# FPGA_IO.net
KiCad netlist of a schematic drawn in Altium Designer
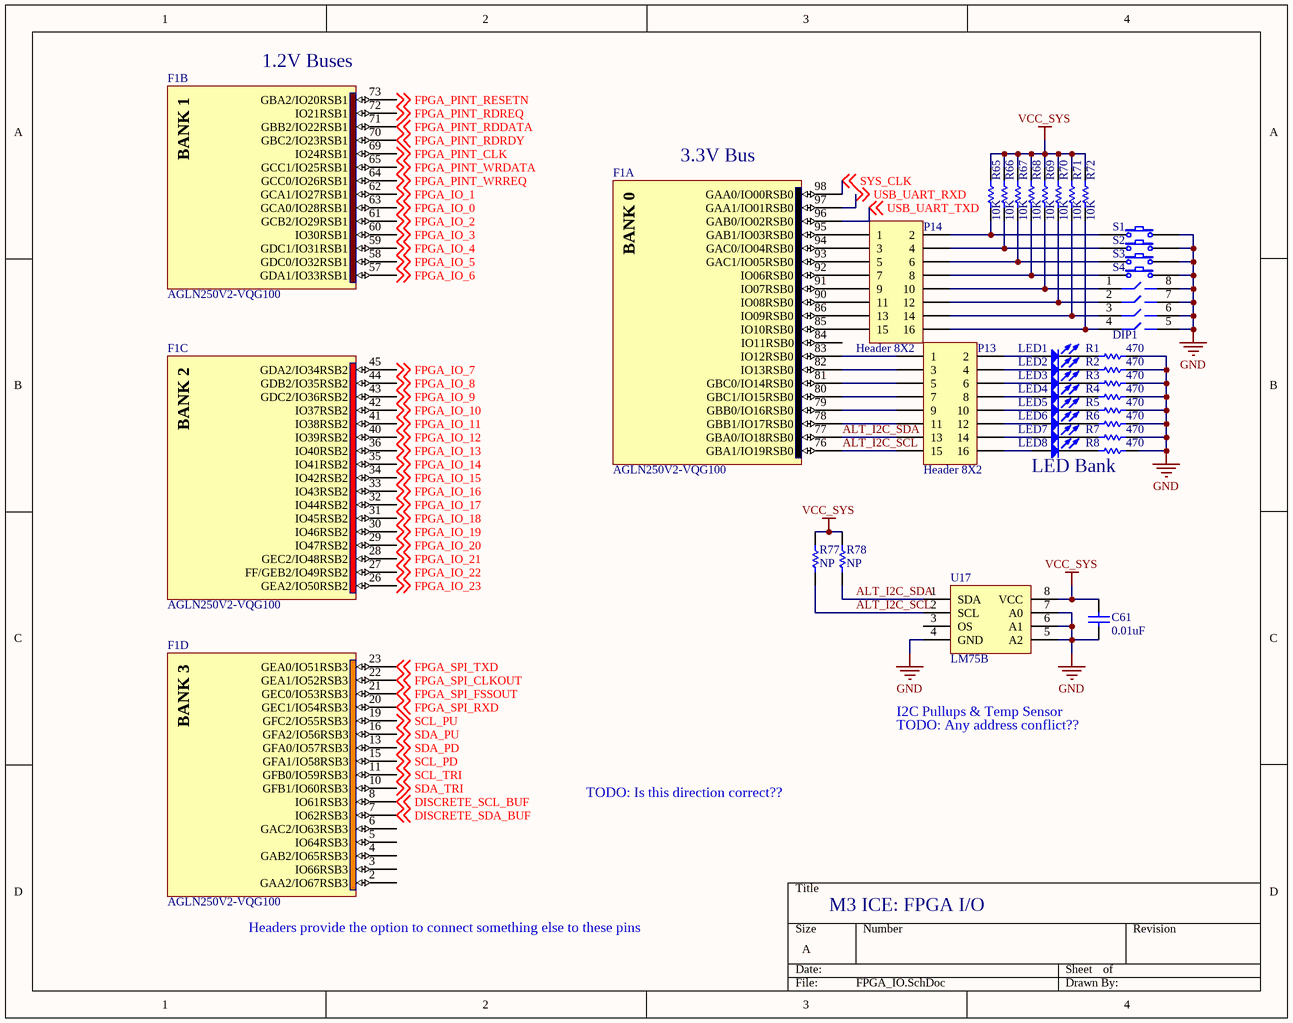
[diagram p0: FPGA_IO.SchDoc]

(export (version "E")
  (design (tool "Eeschema 10.0.6"))
  (components
    (comp (ref "C61")
      (value "0.01uF")
      (footprint "1608[0603]")
      (description "Capacitor (Semiconductor SIM Model)")
      (fields (field (name "Comment") "Cap Semi") (field (name "PUBLISHER") "Altium Limited"))
      (libsource (lib "Miscellaneous Devices") (part "Cap Semi"))
    )
    (comp (ref "DIP1")
      (value "ADE0404")
      (footprint "DIP-8")
      (description "4-DIP Switch")
      (fields (field (name "PUBLISHER") "Altium Limited"))
      (libsource (lib "M3") (part "ADE0404"))
    )
    (comp (ref "F1")
      (value "AGLN250V2-VQG100")
      (footprint "VQ100_N")
      (fields (field (name "PUBLISHER") "Altium Limited"))
      (libsource (lib "Actel IGLOO nano") (part "AGLN250V2-VQG100"))
    )
    (comp (ref "LED1") (value "LED 1206") (footprint "1206_LED") (libsource (lib "M3") (part "LED 1206")))
    (comp (ref "LED2") (value "LED 1206") (footprint "1206_LED") (libsource (lib "M3") (part "LED 1206")))
    (comp (ref "LED3") (value "LED 1206") (footprint "1206_LED") (libsource (lib "M3") (part "LED 1206")))
    (comp (ref "LED4") (value "LED 1206") (footprint "1206_LED") (libsource (lib "M3") (part "LED 1206")))
    (comp (ref "LED5") (value "LED 1206") (footprint "1206_LED") (libsource (lib "M3") (part "LED 1206")))
    (comp (ref "LED6") (value "LED 1206") (footprint "1206_LED") (libsource (lib "M3") (part "LED 1206")))
    (comp (ref "LED7") (value "LED 1206") (footprint "1206_LED") (libsource (lib "M3") (part "LED 1206")))
    (comp (ref "LED8") (value "LED 1206") (footprint "1206_LED") (libsource (lib "M3") (part "LED 1206")))
    (comp (ref "P13")
      (value "Header 8X2")
      (footprint "HDR2X8")
      (description "Header, 8-Pin, Dual row")
      (fields (field (name "PUBLISHER") "Altium Limited"))
      (libsource (lib "Miscellaneous Connectors") (part "Header 8X2"))
    )
    (comp (ref "P14")
      (value "Header 8X2")
      (footprint "HDR2X8")
      (description "Header, 8-Pin, Dual row")
      (fields (field (name "PUBLISHER") "Altium Limited"))
      (libsource (lib "Miscellaneous Connectors") (part "Header 8X2"))
    )
    (comp (ref "R1")
      (value "470")
      (footprint "0603")
      (description "Semiconductor Resistor")
      (fields (field (name "Comment") "Res Chip") (field (name "PUBLISHER") "Altium Limited"))
      (libsource (lib "M3") (part "Res Chip"))
    )
    (comp (ref "R2")
      (value "470")
      (footprint "0603")
      (description "Semiconductor Resistor")
      (fields (field (name "Comment") "Res Chip") (field (name "PUBLISHER") "Altium Limited"))
      (libsource (lib "M3") (part "Res Chip"))
    )
    (comp (ref "R3")
      (value "470")
      (footprint "0603")
      (description "Semiconductor Resistor")
      (fields (field (name "Comment") "Res Chip") (field (name "PUBLISHER") "Altium Limited"))
      (libsource (lib "M3") (part "Res Chip"))
    )
    (comp (ref "R4")
      (value "470")
      (footprint "0603")
      (description "Semiconductor Resistor")
      (fields (field (name "Comment") "Res Chip") (field (name "PUBLISHER") "Altium Limited"))
      (libsource (lib "M3") (part "Res Chip"))
    )
    (comp (ref "R5")
      (value "470")
      (footprint "0603")
      (description "Semiconductor Resistor")
      (fields (field (name "Comment") "Res Chip") (field (name "PUBLISHER") "Altium Limited"))
      (libsource (lib "M3") (part "Res Chip"))
    )
    (comp (ref "R6")
      (value "470")
      (footprint "0603")
      (description "Semiconductor Resistor")
      (fields (field (name "Comment") "Res Chip") (field (name "PUBLISHER") "Altium Limited"))
      (libsource (lib "M3") (part "Res Chip"))
    )
    (comp (ref "R7")
      (value "470")
      (footprint "0603")
      (description "Semiconductor Resistor")
      (fields (field (name "Comment") "Res Chip") (field (name "PUBLISHER") "Altium Limited"))
      (libsource (lib "M3") (part "Res Chip"))
    )
    (comp (ref "R8")
      (value "470")
      (footprint "0603")
      (description "Semiconductor Resistor")
      (fields (field (name "Comment") "Res Chip") (field (name "PUBLISHER") "Altium Limited"))
      (libsource (lib "M3") (part "Res Chip"))
    )
    (comp (ref "R65")
      (value "10K")
      (footprint "0603")
      (description "Semiconductor Resistor")
      (fields (field (name "Comment") "Res Chip") (field (name "PUBLISHER") "Altium Limited"))
      (libsource (lib "M3") (part "Res Chip"))
    )
    (comp (ref "R66")
      (value "10K")
      (footprint "0603")
      (description "Semiconductor Resistor")
      (fields (field (name "Comment") "Res Chip") (field (name "PUBLISHER") "Altium Limited"))
      (libsource (lib "M3") (part "Res Chip"))
    )
    (comp (ref "R67")
      (value "10K")
      (footprint "0603")
      (description "Semiconductor Resistor")
      (fields (field (name "Comment") "Res Chip") (field (name "PUBLISHER") "Altium Limited"))
      (libsource (lib "M3") (part "Res Chip"))
    )
    (comp (ref "R68")
      (value "10K")
      (footprint "0603")
      (description "Semiconductor Resistor")
      (fields (field (name "Comment") "Res Chip") (field (name "PUBLISHER") "Altium Limited"))
      (libsource (lib "M3") (part "Res Chip"))
    )
    (comp (ref "R69")
      (value "10K")
      (footprint "0603")
      (description "Semiconductor Resistor")
      (fields (field (name "Comment") "Res Chip") (field (name "PUBLISHER") "Altium Limited"))
      (libsource (lib "M3") (part "Res Chip"))
    )
    (comp (ref "R70")
      (value "10K")
      (footprint "0603")
      (description "Semiconductor Resistor")
      (fields (field (name "Comment") "Res Chip") (field (name "PUBLISHER") "Altium Limited"))
      (libsource (lib "M3") (part "Res Chip"))
    )
    (comp (ref "R71")
      (value "10K")
      (footprint "0603")
      (description "Semiconductor Resistor")
      (fields (field (name "Comment") "Res Chip") (field (name "PUBLISHER") "Altium Limited"))
      (libsource (lib "M3") (part "Res Chip"))
    )
    (comp (ref "R72")
      (value "10K")
      (footprint "0603")
      (description "Semiconductor Resistor")
      (fields (field (name "Comment") "Res Chip") (field (name "PUBLISHER") "Altium Limited"))
      (libsource (lib "M3") (part "Res Chip"))
    )
    (comp (ref "R77")
      (value "NP")
      (footprint "0603")
      (description "Semiconductor Resistor")
      (fields (field (name "Comment") "Res Chip") (field (name "PUBLISHER") "Altium Limited"))
      (libsource (lib "M3") (part "Res Chip"))
    )
    (comp (ref "R78")
      (value "NP")
      (footprint "0603")
      (description "Semiconductor Resistor")
      (fields (field (name "Comment") "Res Chip") (field (name "PUBLISHER") "Altium Limited"))
      (libsource (lib "M3") (part "Res Chip"))
    )
    (comp (ref "S1")
      (value "EVQ-PAE04M")
      (footprint "EVQPA")
      (description "Switch Push")
      (fields (field (name "PUBLISHER") "Altium Limited"))
      (libsource (lib "M3") (part "EVQ-PAE04M"))
    )
    (comp (ref "S2")
      (value "EVQ-PAE04M")
      (footprint "EVQPA")
      (description "Switch Push")
      (fields (field (name "PUBLISHER") "Altium Limited"))
      (libsource (lib "M3") (part "EVQ-PAE04M"))
    )
    (comp (ref "S3")
      (value "EVQ-PAE04M")
      (footprint "EVQPA")
      (description "Switch Push")
      (fields (field (name "PUBLISHER") "Altium Limited"))
      (libsource (lib "M3") (part "EVQ-PAE04M"))
    )
    (comp (ref "S4")
      (value "EVQ-PAE04M")
      (footprint "EVQPA")
      (description "Switch Push")
      (fields (field (name "PUBLISHER") "Altium Limited"))
      (libsource (lib "M3") (part "EVQ-PAE04M"))
    )
    (comp (ref "U17")
      (value "LM75B")
      (footprint "SO8")
      (description "I2C Temp Sensor")
      (libsource (lib "M3") (part "LM75B"))
    )
  )
  (nets
    (net (code "1") (name "/ALT_I2C_SCL") (class "Default")
      (node (ref "F1") (pin "76") (pinfunction "GBA1/IO19RSB0_76") (pintype "bidirectional"))
      (node (ref "P13") (pin "15") (pinfunction "15_15") (pintype "passive"))
      (node (ref "R77") (pin "2") (pinfunction "2_2") (pintype "passive"))
      (node (ref "U17") (pin "2") (pinfunction "SCL_2") (pintype "passive"))
    )
    (net (code "2") (name "/ALT_I2C_SDA") (class "Default")
      (node (ref "F1") (pin "77") (pinfunction "GBA0/IO18RSB0_77") (pintype "bidirectional"))
      (node (ref "P13") (pin "13") (pinfunction "13_13") (pintype "passive"))
      (node (ref "R78") (pin "2") (pinfunction "2_2") (pintype "passive"))
      (node (ref "U17") (pin "1") (pinfunction "SDA_1") (pintype "passive"))
    )
    (net (code "3") (name "DISCRETE_SCL_BUF") (class "Default")
      (node (ref "F1") (pin "8") (pinfunction "IO61RSB3_8") (pintype "bidirectional"))
    )
    (net (code "4") (name "DISCRETE_SDA_BUF") (class "Default")
      (node (ref "F1") (pin "7") (pinfunction "IO62RSB3_7") (pintype "bidirectional"))
    )
    (net (code "5") (name "FPGA_IO_0") (class "Default")
      (node (ref "F1") (pin "63") (pinfunction "GCA0/IO28RSB1_63") (pintype "bidirectional"))
    )
    (net (code "6") (name "FPGA_IO_1") (class "Default")
      (node (ref "F1") (pin "62") (pinfunction "GCA1/IO27RSB1_62") (pintype "bidirectional"))
    )
    (net (code "7") (name "FPGA_IO_2") (class "Default")
      (node (ref "F1") (pin "61") (pinfunction "GCB2/IO29RSB1_61") (pintype "bidirectional"))
    )
    (net (code "8") (name "FPGA_IO_3") (class "Default")
      (node (ref "F1") (pin "60") (pinfunction "IO30RSB1_60") (pintype "bidirectional"))
    )
    (net (code "9") (name "FPGA_IO_4") (class "Default")
      (node (ref "F1") (pin "59") (pinfunction "GDC1/IO31RSB1_59") (pintype "bidirectional"))
    )
    (net (code "10") (name "FPGA_IO_5") (class "Default")
      (node (ref "F1") (pin "58") (pinfunction "GDC0/IO32RSB1_58") (pintype "bidirectional"))
    )
    (net (code "11") (name "FPGA_IO_6") (class "Default")
      (node (ref "F1") (pin "57") (pinfunction "GDA1/IO33RSB1_57") (pintype "bidirectional"))
    )
    (net (code "12") (name "FPGA_IO_7") (class "Default")
      (node (ref "F1") (pin "45") (pinfunction "GDA2/IO34RSB2_45") (pintype "bidirectional"))
    )
    (net (code "13") (name "FPGA_IO_8") (class "Default")
      (node (ref "F1") (pin "44") (pinfunction "GDB2/IO35RSB2_44") (pintype "bidirectional"))
    )
    (net (code "14") (name "FPGA_IO_9") (class "Default")
      (node (ref "F1") (pin "43") (pinfunction "GDC2/IO36RSB2_43") (pintype "bidirectional"))
    )
    (net (code "15") (name "FPGA_IO_10") (class "Default")
      (node (ref "F1") (pin "42") (pinfunction "IO37RSB2_42") (pintype "bidirectional"))
    )
    (net (code "16") (name "FPGA_IO_11") (class "Default")
      (node (ref "F1") (pin "41") (pinfunction "IO38RSB2_41") (pintype "bidirectional"))
    )
    (net (code "17") (name "FPGA_IO_12") (class "Default")
      (node (ref "F1") (pin "40") (pinfunction "IO39RSB2_40") (pintype "bidirectional"))
    )
    (net (code "18") (name "FPGA_IO_13") (class "Default")
      (node (ref "F1") (pin "36") (pinfunction "IO40RSB2_36") (pintype "bidirectional"))
    )
    (net (code "19") (name "FPGA_IO_14") (class "Default")
      (node (ref "F1") (pin "35") (pinfunction "IO41RSB2_35") (pintype "bidirectional"))
    )
    (net (code "20") (name "FPGA_IO_15") (class "Default")
      (node (ref "F1") (pin "34") (pinfunction "IO42RSB2_34") (pintype "bidirectional"))
    )
    (net (code "21") (name "FPGA_IO_16") (class "Default")
      (node (ref "F1") (pin "33") (pinfunction "IO43RSB2_33") (pintype "bidirectional"))
    )
    (net (code "22") (name "FPGA_IO_17") (class "Default")
      (node (ref "F1") (pin "32") (pinfunction "IO44RSB2_32") (pintype "bidirectional"))
    )
    (net (code "23") (name "FPGA_IO_18") (class "Default")
      (node (ref "F1") (pin "31") (pinfunction "IO45RSB2_31") (pintype "bidirectional"))
    )
    (net (code "24") (name "FPGA_IO_19") (class "Default")
      (node (ref "F1") (pin "30") (pinfunction "IO46RSB2_30") (pintype "bidirectional"))
    )
    (net (code "25") (name "FPGA_IO_20") (class "Default")
      (node (ref "F1") (pin "29") (pinfunction "IO47RSB2_29") (pintype "bidirectional"))
    )
    (net (code "26") (name "FPGA_IO_21") (class "Default")
      (node (ref "F1") (pin "28") (pinfunction "GEC2/IO48RSB2_28") (pintype "bidirectional"))
    )
    (net (code "27") (name "FPGA_IO_22") (class "Default")
      (node (ref "F1") (pin "27") (pinfunction "FF/GEB2/IO49RSB2_27") (pintype "bidirectional"))
    )
    (net (code "28") (name "FPGA_IO_23") (class "Default")
      (node (ref "F1") (pin "26") (pinfunction "GEA2/IO50RSB2_26") (pintype "bidirectional"))
    )
    (net (code "29") (name "FPGA_PINT_CLK") (class "Default")
      (node (ref "F1") (pin "69") (pinfunction "IO24RSB1_69") (pintype "bidirectional"))
    )
    (net (code "30") (name "FPGA_PINT_RDDATA") (class "Default")
      (node (ref "F1") (pin "71") (pinfunction "GBB2/IO22RSB1_71") (pintype "bidirectional"))
    )
    (net (code "31") (name "FPGA_PINT_RDRDY") (class "Default")
      (node (ref "F1") (pin "70") (pinfunction "GBC2/IO23RSB1_70") (pintype "bidirectional"))
    )
    (net (code "32") (name "FPGA_PINT_RDREQ") (class "Default")
      (node (ref "F1") (pin "72") (pinfunction "IO21RSB1_72") (pintype "bidirectional"))
    )
    (net (code "33") (name "FPGA_PINT_RESETN") (class "Default")
      (node (ref "F1") (pin "73") (pinfunction "GBA2/IO20RSB1_73") (pintype "bidirectional"))
    )
    (net (code "34") (name "FPGA_PINT_WRDATA") (class "Default")
      (node (ref "F1") (pin "65") (pinfunction "GCC1/IO25RSB1_65") (pintype "bidirectional"))
    )
    (net (code "35") (name "FPGA_PINT_WRREQ") (class "Default")
      (node (ref "F1") (pin "64") (pinfunction "GCC0/IO26RSB1_64") (pintype "bidirectional"))
    )
    (net (code "36") (name "FPGA_SPI_CLKOUT") (class "Default")
      (node (ref "F1") (pin "22") (pinfunction "GEA1/IO52RSB3_22") (pintype "bidirectional"))
    )
    (net (code "37") (name "FPGA_SPI_FSSOUT") (class "Default")
      (node (ref "F1") (pin "21") (pinfunction "GEC0/IO53RSB3_21") (pintype "bidirectional"))
    )
    (net (code "38") (name "FPGA_SPI_RXD") (class "Default")
      (node (ref "F1") (pin "20") (pinfunction "GEC1/IO54RSB3_20") (pintype "bidirectional"))
    )
    (net (code "39") (name "FPGA_SPI_TXD") (class "Default")
      (node (ref "F1") (pin "23") (pinfunction "GEA0/IO51RSB3_23") (pintype "bidirectional"))
    )
    (net (code "40") (name "GND") (class "Default")
      (node (ref "C61") (pin "1") (pinfunction "1_1") (pintype "passive"))
      (node (ref "DIP1") (pin "5") (pinfunction "5_5") (pintype "passive"))
      (node (ref "DIP1") (pin "6") (pinfunction "6_6") (pintype "passive"))
      (node (ref "DIP1") (pin "7") (pinfunction "7_7") (pintype "passive"))
      (node (ref "DIP1") (pin "8") (pinfunction "8_8") (pintype "passive"))
      (node (ref "R1") (pin "1") (pinfunction "1_1") (pintype "passive"))
      (node (ref "R2") (pin "1") (pinfunction "1_1") (pintype "passive"))
      (node (ref "R3") (pin "1") (pinfunction "1_1") (pintype "passive"))
      (node (ref "R4") (pin "1") (pinfunction "1_1") (pintype "passive"))
      (node (ref "R5") (pin "1") (pinfunction "1_1") (pintype "passive"))
      (node (ref "R6") (pin "1") (pinfunction "1_1") (pintype "passive"))
      (node (ref "R7") (pin "1") (pinfunction "1_1") (pintype "passive"))
      (node (ref "R8") (pin "1") (pinfunction "1_1") (pintype "passive"))
      (node (ref "S1") (pin "2") (pinfunction "2_2") (pintype "passive"))
      (node (ref "S2") (pin "2") (pinfunction "2_2") (pintype "passive"))
      (node (ref "S3") (pin "2") (pinfunction "2_2") (pintype "passive"))
      (node (ref "S4") (pin "2") (pinfunction "2_2") (pintype "passive"))
      (node (ref "U17") (pin "4") (pinfunction "GND_4") (pintype "passive"))
      (node (ref "U17") (pin "5") (pinfunction "A2_5") (pintype "passive"))
      (node (ref "U17") (pin "6") (pinfunction "A1_6") (pintype "passive"))
      (node (ref "U17") (pin "7") (pinfunction "A0_7") (pintype "passive"))
    )
    (net (code "41") (name "Net-(DIP1-Pad1)") (class "Default")
      (node (ref "DIP1") (pin "1") (pinfunction "1_1") (pintype "passive"))
      (node (ref "P14") (pin "10") (pinfunction "10_10") (pintype "passive"))
      (node (ref "R69") (pin "2") (pinfunction "2_2") (pintype "passive"))
    )
    (net (code "42") (name "Net-(DIP1-Pad2)") (class "Default")
      (node (ref "DIP1") (pin "2") (pinfunction "2_2") (pintype "passive"))
      (node (ref "P14") (pin "12") (pinfunction "12_12") (pintype "passive"))
      (node (ref "R70") (pin "2") (pinfunction "2_2") (pintype "passive"))
    )
    (net (code "43") (name "Net-(DIP1-Pad3)") (class "Default")
      (node (ref "DIP1") (pin "3") (pinfunction "3_3") (pintype "passive"))
      (node (ref "P14") (pin "14") (pinfunction "14_14") (pintype "passive"))
      (node (ref "R71") (pin "2") (pinfunction "2_2") (pintype "passive"))
    )
    (net (code "44") (name "Net-(DIP1-Pad4)") (class "Default")
      (node (ref "DIP1") (pin "4") (pinfunction "4_4") (pintype "passive"))
      (node (ref "P14") (pin "16") (pinfunction "16_16") (pintype "passive"))
      (node (ref "R72") (pin "2") (pinfunction "2_2") (pintype "passive"))
    )
    (net (code "45") (name "Net-(F1A-GAB1{slash}IO03RSB0)") (class "Default")
      (node (ref "F1") (pin "95") (pinfunction "GAB1/IO03RSB0_95") (pintype "bidirectional"))
      (node (ref "P14") (pin "1") (pinfunction "1_1") (pintype "passive"))
    )
    (net (code "46") (name "Net-(F1A-GAC0{slash}IO04RSB0)") (class "Default")
      (node (ref "F1") (pin "94") (pinfunction "GAC0/IO04RSB0_94") (pintype "bidirectional"))
      (node (ref "P14") (pin "3") (pinfunction "3_3") (pintype "passive"))
    )
    (net (code "47") (name "Net-(F1A-GAC1{slash}IO05RSB0)") (class "Default")
      (node (ref "F1") (pin "93") (pinfunction "GAC1/IO05RSB0_93") (pintype "bidirectional"))
      (node (ref "P14") (pin "5") (pinfunction "5_5") (pintype "passive"))
    )
    (net (code "48") (name "Net-(F1A-GBB0{slash}IO16RSB0)") (class "Default")
      (node (ref "F1") (pin "79") (pinfunction "GBB0/IO16RSB0_79") (pintype "bidirectional"))
      (node (ref "P13") (pin "9") (pinfunction "9_9") (pintype "passive"))
    )
    (net (code "49") (name "Net-(F1A-GBB1{slash}IO17RSB0)") (class "Default")
      (node (ref "F1") (pin "78") (pinfunction "GBB1/IO17RSB0_78") (pintype "bidirectional"))
      (node (ref "P13") (pin "11") (pinfunction "11_11") (pintype "passive"))
    )
    (net (code "50") (name "Net-(F1A-GBC0{slash}IO14RSB0)") (class "Default")
      (node (ref "F1") (pin "81") (pinfunction "GBC0/IO14RSB0_81") (pintype "bidirectional"))
      (node (ref "P13") (pin "5") (pinfunction "5_5") (pintype "passive"))
    )
    (net (code "51") (name "Net-(F1A-GBC1{slash}IO15RSB0)") (class "Default")
      (node (ref "F1") (pin "80") (pinfunction "GBC1/IO15RSB0_80") (pintype "bidirectional"))
      (node (ref "P13") (pin "7") (pinfunction "7_7") (pintype "passive"))
    )
    (net (code "52") (name "Net-(F1A-IO06RSB0)") (class "Default")
      (node (ref "F1") (pin "92") (pinfunction "IO06RSB0_92") (pintype "bidirectional"))
      (node (ref "P14") (pin "7") (pinfunction "7_7") (pintype "passive"))
    )
    (net (code "53") (name "Net-(F1A-IO07RSB0)") (class "Default")
      (node (ref "F1") (pin "91") (pinfunction "IO07RSB0_91") (pintype "bidirectional"))
      (node (ref "P14") (pin "9") (pinfunction "9_9") (pintype "passive"))
    )
    (net (code "54") (name "Net-(F1A-IO08RSB0)") (class "Default")
      (node (ref "F1") (pin "90") (pinfunction "IO08RSB0_90") (pintype "bidirectional"))
      (node (ref "P14") (pin "11") (pinfunction "11_11") (pintype "passive"))
    )
    (net (code "55") (name "Net-(F1A-IO09RSB0)") (class "Default")
      (node (ref "F1") (pin "86") (pinfunction "IO09RSB0_86") (pintype "bidirectional"))
      (node (ref "P14") (pin "13") (pinfunction "13_13") (pintype "passive"))
    )
    (net (code "56") (name "Net-(F1A-IO10RSB0)") (class "Default")
      (node (ref "F1") (pin "85") (pinfunction "IO10RSB0_85") (pintype "bidirectional"))
      (node (ref "P14") (pin "15") (pinfunction "15_15") (pintype "passive"))
    )
    (net (code "57") (name "Net-(F1A-IO12RSB0)") (class "Default")
      (node (ref "F1") (pin "83") (pinfunction "IO12RSB0_83") (pintype "bidirectional"))
      (node (ref "P13") (pin "1") (pinfunction "1_1") (pintype "passive"))
    )
    (net (code "58") (name "Net-(F1A-IO13RSB0)") (class "Default")
      (node (ref "F1") (pin "82") (pinfunction "IO13RSB0_82") (pintype "bidirectional"))
      (node (ref "P13") (pin "3") (pinfunction "3_3") (pintype "passive"))
    )
    (net (code "59") (name "Net-(LED1-A)") (class "Default")
      (node (ref "LED1") (pin "1") (pinfunction "A_1") (pintype "passive"))
      (node (ref "P13") (pin "2") (pinfunction "2_2") (pintype "passive"))
    )
    (net (code "60") (name "Net-(LED1-K)") (class "Default")
      (node (ref "LED1") (pin "2") (pinfunction "K_2") (pintype "passive"))
      (node (ref "R1") (pin "2") (pinfunction "2_2") (pintype "passive"))
    )
    (net (code "61") (name "Net-(LED2-A)") (class "Default")
      (node (ref "LED2") (pin "1") (pinfunction "A_1") (pintype "passive"))
      (node (ref "P13") (pin "4") (pinfunction "4_4") (pintype "passive"))
    )
    (net (code "62") (name "Net-(LED2-K)") (class "Default")
      (node (ref "LED2") (pin "2") (pinfunction "K_2") (pintype "passive"))
      (node (ref "R2") (pin "2") (pinfunction "2_2") (pintype "passive"))
    )
    (net (code "63") (name "Net-(LED3-A)") (class "Default")
      (node (ref "LED3") (pin "1") (pinfunction "A_1") (pintype "passive"))
      (node (ref "P13") (pin "6") (pinfunction "6_6") (pintype "passive"))
    )
    (net (code "64") (name "Net-(LED3-K)") (class "Default")
      (node (ref "LED3") (pin "2") (pinfunction "K_2") (pintype "passive"))
      (node (ref "R3") (pin "2") (pinfunction "2_2") (pintype "passive"))
    )
    (net (code "65") (name "Net-(LED4-A)") (class "Default")
      (node (ref "LED4") (pin "1") (pinfunction "A_1") (pintype "passive"))
      (node (ref "P13") (pin "8") (pinfunction "8_8") (pintype "passive"))
    )
    (net (code "66") (name "Net-(LED4-K)") (class "Default")
      (node (ref "LED4") (pin "2") (pinfunction "K_2") (pintype "passive"))
      (node (ref "R4") (pin "2") (pinfunction "2_2") (pintype "passive"))
    )
    (net (code "67") (name "Net-(LED5-A)") (class "Default")
      (node (ref "LED5") (pin "1") (pinfunction "A_1") (pintype "passive"))
      (node (ref "P13") (pin "10") (pinfunction "10_10") (pintype "passive"))
    )
    (net (code "68") (name "Net-(LED5-K)") (class "Default")
      (node (ref "LED5") (pin "2") (pinfunction "K_2") (pintype "passive"))
      (node (ref "R5") (pin "2") (pinfunction "2_2") (pintype "passive"))
    )
    (net (code "69") (name "Net-(LED6-A)") (class "Default")
      (node (ref "LED6") (pin "1") (pinfunction "A_1") (pintype "passive"))
      (node (ref "P13") (pin "12") (pinfunction "12_12") (pintype "passive"))
    )
    (net (code "70") (name "Net-(LED6-K)") (class "Default")
      (node (ref "LED6") (pin "2") (pinfunction "K_2") (pintype "passive"))
      (node (ref "R6") (pin "2") (pinfunction "2_2") (pintype "passive"))
    )
    (net (code "71") (name "Net-(LED7-A)") (class "Default")
      (node (ref "LED7") (pin "1") (pinfunction "A_1") (pintype "passive"))
      (node (ref "P13") (pin "14") (pinfunction "14_14") (pintype "passive"))
    )
    (net (code "72") (name "Net-(LED7-K)") (class "Default")
      (node (ref "LED7") (pin "2") (pinfunction "K_2") (pintype "passive"))
      (node (ref "R7") (pin "2") (pinfunction "2_2") (pintype "passive"))
    )
    (net (code "73") (name "Net-(LED8-A)") (class "Default")
      (node (ref "LED8") (pin "1") (pinfunction "A_1") (pintype "passive"))
      (node (ref "P13") (pin "16") (pinfunction "16_16") (pintype "passive"))
    )
    (net (code "74") (name "Net-(LED8-K)") (class "Default")
      (node (ref "LED8") (pin "2") (pinfunction "K_2") (pintype "passive"))
      (node (ref "R8") (pin "2") (pinfunction "2_2") (pintype "passive"))
    )
    (net (code "75") (name "Net-(P14-Pad2)") (class "Default")
      (node (ref "P14") (pin "2") (pinfunction "2_2") (pintype "passive"))
      (node (ref "R65") (pin "2") (pinfunction "2_2") (pintype "passive"))
      (node (ref "S1") (pin "1") (pinfunction "1_1") (pintype "passive"))
    )
    (net (code "76") (name "Net-(P14-Pad4)") (class "Default")
      (node (ref "P14") (pin "4") (pinfunction "4_4") (pintype "passive"))
      (node (ref "R66") (pin "2") (pinfunction "2_2") (pintype "passive"))
      (node (ref "S2") (pin "1") (pinfunction "1_1") (pintype "passive"))
    )
    (net (code "77") (name "Net-(P14-Pad6)") (class "Default")
      (node (ref "P14") (pin "6") (pinfunction "6_6") (pintype "passive"))
      (node (ref "R67") (pin "2") (pinfunction "2_2") (pintype "passive"))
      (node (ref "S3") (pin "1") (pinfunction "1_1") (pintype "passive"))
    )
    (net (code "78") (name "Net-(P14-Pad8)") (class "Default")
      (node (ref "P14") (pin "8") (pinfunction "8_8") (pintype "passive"))
      (node (ref "R68") (pin "2") (pinfunction "2_2") (pintype "passive"))
      (node (ref "S4") (pin "1") (pinfunction "1_1") (pintype "passive"))
    )
    (net (code "79") (name "SCL_PD") (class "Default")
      (node (ref "F1") (pin "15") (pinfunction "GFA1/IO58RSB3_15") (pintype "bidirectional"))
    )
    (net (code "80") (name "SCL_PU") (class "Default")
      (node (ref "F1") (pin "19") (pinfunction "GFC2/IO55RSB3_19") (pintype "bidirectional"))
    )
    (net (code "81") (name "SCL_TRI") (class "Default")
      (node (ref "F1") (pin "11") (pinfunction "GFB0/IO59RSB3_11") (pintype "bidirectional"))
    )
    (net (code "82") (name "SDA_PD") (class "Default")
      (node (ref "F1") (pin "13") (pinfunction "GFA0/IO57RSB3_13") (pintype "bidirectional"))
    )
    (net (code "83") (name "SDA_PU") (class "Default")
      (node (ref "F1") (pin "16") (pinfunction "GFA2/IO56RSB3_16") (pintype "bidirectional"))
    )
    (net (code "84") (name "SDA_TRI") (class "Default")
      (node (ref "F1") (pin "10") (pinfunction "GFB1/IO60RSB3_10") (pintype "bidirectional"))
    )
    (net (code "85") (name "SYS_CLK") (class "Default")
      (node (ref "F1") (pin "98") (pinfunction "GAA0/IO00RSB0_98") (pintype "bidirectional"))
    )
    (net (code "86") (name "USB_UART_RXD") (class "Default")
      (node (ref "F1") (pin "97") (pinfunction "GAA1/IO01RSB0_97") (pintype "bidirectional"))
    )
    (net (code "87") (name "USB_UART_TXD") (class "Default")
      (node (ref "F1") (pin "96") (pinfunction "GAB0/IO02RSB0_96") (pintype "bidirectional"))
    )
    (net (code "88") (name "VCC_SYS") (class "Default")
      (node (ref "C61") (pin "2") (pinfunction "2_2") (pintype "passive"))
      (node (ref "R65") (pin "1") (pinfunction "1_1") (pintype "passive"))
      (node (ref "R66") (pin "1") (pinfunction "1_1") (pintype "passive"))
      (node (ref "R67") (pin "1") (pinfunction "1_1") (pintype "passive"))
      (node (ref "R68") (pin "1") (pinfunction "1_1") (pintype "passive"))
      (node (ref "R69") (pin "1") (pinfunction "1_1") (pintype "passive"))
      (node (ref "R70") (pin "1") (pinfunction "1_1") (pintype "passive"))
      (node (ref "R71") (pin "1") (pinfunction "1_1") (pintype "passive"))
      (node (ref "R72") (pin "1") (pinfunction "1_1") (pintype "passive"))
      (node (ref "R77") (pin "1") (pinfunction "1_1") (pintype "passive"))
      (node (ref "R78") (pin "1") (pinfunction "1_1") (pintype "passive"))
      (node (ref "U17") (pin "8") (pinfunction "VCC_8") (pintype "passive"))
    )
    (net (code "89") (name "unconnected-(F1A-IO11RSB0-Pad84)") (class "Default")
      (node (ref "F1") (pin "84") (pinfunction "IO11RSB0_84") (pintype "bidirectional"))
    )
    (net (code "90") (name "unconnected-(F1D-GAA2{slash}IO67RSB3-Pad2)") (class "Default")
      (node (ref "F1") (pin "2") (pinfunction "GAA2/IO67RSB3_2") (pintype "bidirectional"))
    )
    (net (code "91") (name "unconnected-(F1D-GAB2{slash}IO65RSB3-Pad4)") (class "Default")
      (node (ref "F1") (pin "4") (pinfunction "GAB2/IO65RSB3_4") (pintype "bidirectional"))
    )
    (net (code "92") (name "unconnected-(F1D-GAC2{slash}IO63RSB3-Pad6)") (class "Default")
      (node (ref "F1") (pin "6") (pinfunction "GAC2/IO63RSB3_6") (pintype "bidirectional"))
    )
    (net (code "93") (name "unconnected-(F1D-IO64RSB3-Pad5)") (class "Default")
      (node (ref "F1") (pin "5") (pinfunction "IO64RSB3_5") (pintype "bidirectional"))
    )
    (net (code "94") (name "unconnected-(F1D-IO66RSB3-Pad3)") (class "Default")
      (node (ref "F1") (pin "3") (pinfunction "IO66RSB3_3") (pintype "bidirectional"))
    )
    (net (code "95") (name "unconnected-(U17-OS-Pad3)") (class "Default")
      (node (ref "U17") (pin "3") (pinfunction "OS_3") (pintype "passive"))
    )
  )
)
